# esp3d_8266.net
KiCad netlist of a schematic drawn in EAGLE
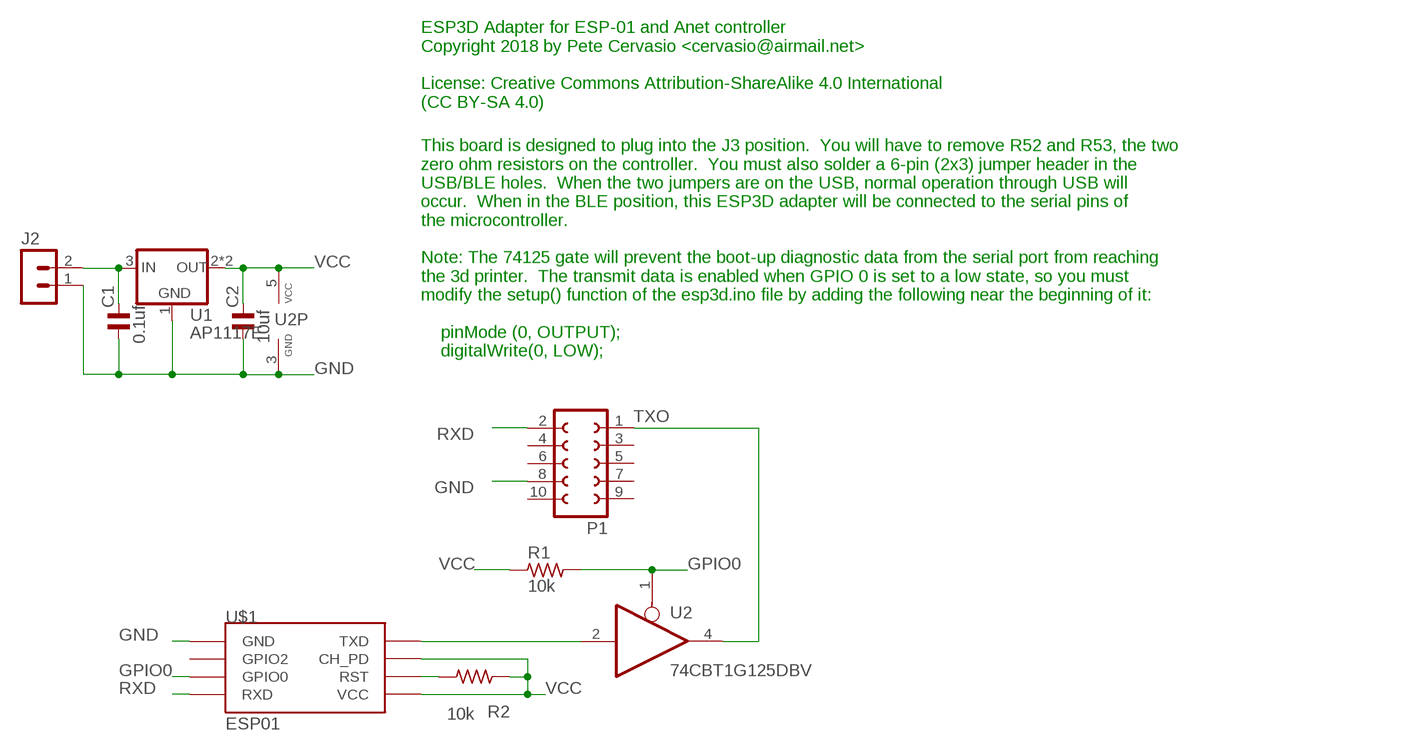
[diagram p0: schematic, sheet 1]

(export (version "E")
  (design (tool "Eeschema 10.0.6"))
  (components
    (comp (ref "C1")
      (value "0.1uf")
      (footprint "eagle-import:C0805")
      (libsource (lib "eagle-import") (part "C_0805"))
    )
    (comp (ref "C2")
      (value "10uf")
      (footprint "eagle-import:C0805")
      (libsource (lib "eagle-import") (part "C_0805"))
    )
    (comp (ref "J2")
      (value "MA02-1")
      (footprint "eagle-import:MA02-1")
      (libsource (lib "eagle-import") (part "MA02-1"))
    )
    (comp (ref "P1")
      (value "FE05-2")
      (footprint "eagle-import:FE05-2")
      (libsource (lib "eagle-import") (part "FE05-2"))
    )
    (comp (ref "R1")
      (value "10k")
      (footprint "eagle-import:R0805")
      (libsource (lib "eagle-import") (part "R_0805"))
    )
    (comp (ref "R2")
      (value "10k")
      (footprint "eagle-import:R0805")
      (libsource (lib "eagle-import") (part "R_0805"))
    )
    (comp (ref "U$1")
      (value "ESP01")
      (footprint "eagle-import:ESP01")
      (libsource (lib "eagle-import") (part "ESP01"))
    )
    (comp (ref "U1")
      (value "AP1117E")
      (footprint "eagle-import:SOT223")
      (libsource (lib "eagle-import") (part "AP1117E"))
    )
    (comp (ref "U2")
      (value "74CBT1G125DBV")
      (footprint "eagle-import:SOT23-5")
      (libsource (lib "eagle-import") (part "741G125DBVCBT"))
    )
  )
  (nets
    (net (code "1") (name "/GND") (class "Default")
      (node (ref "C1") (pin "1") (pinfunction "1_1") (pintype "passive"))
      (node (ref "C2") (pin "1") (pinfunction "1_1") (pintype "passive"))
      (node (ref "J2") (pin "1") (pinfunction "1_1") (pintype "passive"))
      (node (ref "P1") (pin "8") (pinfunction "8_8") (pintype "passive"))
      (node (ref "U$1") (pin "GND") (pinfunction "GND_GND") (pintype "bidirectional"))
      (node (ref "U1") (pin "1") (pinfunction "GND_1") (pintype "input"))
      (node (ref "U2") (pin "3") (pinfunction "GND_3") (pintype "power_in"))
    )
    (net (code "2") (name "/GPIO0") (class "Default")
      (node (ref "R1") (pin "2") (pinfunction "2_2") (pintype "passive"))
      (node (ref "U$1") (pin "GPIO0") (pinfunction "GPIO0_GPIO0") (pintype "bidirectional"))
      (node (ref "U2") (pin "1") (pinfunction "OE_1") (pintype "input"))
    )
    (net (code "3") (name "/RXD") (class "Default")
      (node (ref "P1") (pin "2") (pinfunction "2_2") (pintype "passive"))
      (node (ref "U$1") (pin "RX") (pinfunction "RXD_RX") (pintype "bidirectional"))
    )
    (net (code "4") (name "/TXO") (class "Default")
      (node (ref "P1") (pin "1") (pinfunction "1_1") (pintype "passive"))
      (node (ref "U2") (pin "4") (pinfunction "O_4") (pintype "tri_state"))
    )
    (net (code "5") (name "/VCC") (class "Default")
      (node (ref "C2") (pin "2") (pinfunction "2_2") (pintype "passive"))
      (node (ref "R1") (pin "1") (pinfunction "1_1") (pintype "passive"))
      (node (ref "R2") (pin "1") (pinfunction "1_1") (pintype "passive"))
      (node (ref "U$1") (pin "CH_PD") (pinfunction "CH_PD_CH_PD") (pintype "bidirectional"))
      (node (ref "U$1") (pin "VCC") (pinfunction "VCC_VCC") (pintype "bidirectional"))
      (node (ref "U1") (pin "2") (pinfunction "OUT_2") (pintype "passive"))
      (node (ref "U1") (pin "4") (pinfunction "OUT_4") (pintype "passive"))
      (node (ref "U2") (pin "5") (pinfunction "VCC_5") (pintype "power_in"))
    )
    (net (code "6") (name "Net-(R2-Pad2)") (class "Default")
      (node (ref "R2") (pin "2") (pinfunction "2_2") (pintype "passive"))
      (node (ref "U$1") (pin "RST") (pinfunction "RST_RST") (pintype "bidirectional"))
    )
    (net (code "7") (name "Net-(U$1-TXD)") (class "Default")
      (node (ref "U$1") (pin "TX") (pinfunction "TXD_TX") (pintype "bidirectional"))
      (node (ref "U2") (pin "2") (pinfunction "I_2") (pintype "input"))
    )
    (net (code "8") (name "Net-(U1-IN)") (class "Default")
      (node (ref "C1") (pin "2") (pinfunction "2_2") (pintype "passive"))
      (node (ref "J2") (pin "2") (pinfunction "2_2") (pintype "passive"))
      (node (ref "U1") (pin "3") (pinfunction "IN_3") (pintype "input"))
    )
    (net (code "9") (name "unconnected-(P1-Pad3)") (class "Default")
      (node (ref "P1") (pin "3") (pinfunction "3_3") (pintype "passive"))
    )
    (net (code "10") (name "unconnected-(P1-Pad4)") (class "Default")
      (node (ref "P1") (pin "4") (pinfunction "4_4") (pintype "passive"))
    )
    (net (code "11") (name "unconnected-(P1-Pad5)") (class "Default")
      (node (ref "P1") (pin "5") (pinfunction "5_5") (pintype "passive"))
    )
    (net (code "12") (name "unconnected-(P1-Pad6)") (class "Default")
      (node (ref "P1") (pin "6") (pinfunction "6_6") (pintype "passive"))
    )
    (net (code "13") (name "unconnected-(P1-Pad7)") (class "Default")
      (node (ref "P1") (pin "7") (pinfunction "7_7") (pintype "passive"))
    )
    (net (code "14") (name "unconnected-(P1-Pad9)") (class "Default")
      (node (ref "P1") (pin "9") (pinfunction "9_9") (pintype "passive"))
    )
    (net (code "15") (name "unconnected-(P1-Pad10)") (class "Default")
      (node (ref "P1") (pin "10") (pinfunction "10_10") (pintype "passive"))
    )
    (net (code "16") (name "unconnected-(U$1-PadGPIO2)") (class "Default")
      (node (ref "U$1") (pin "GPIO2") (pinfunction "GPIO2_GPIO2") (pintype "bidirectional"))
    )
  )
)
